# 03_-_Lattice_FPGA.net
KiCad netlist of a schematic drawn in Altium Designer
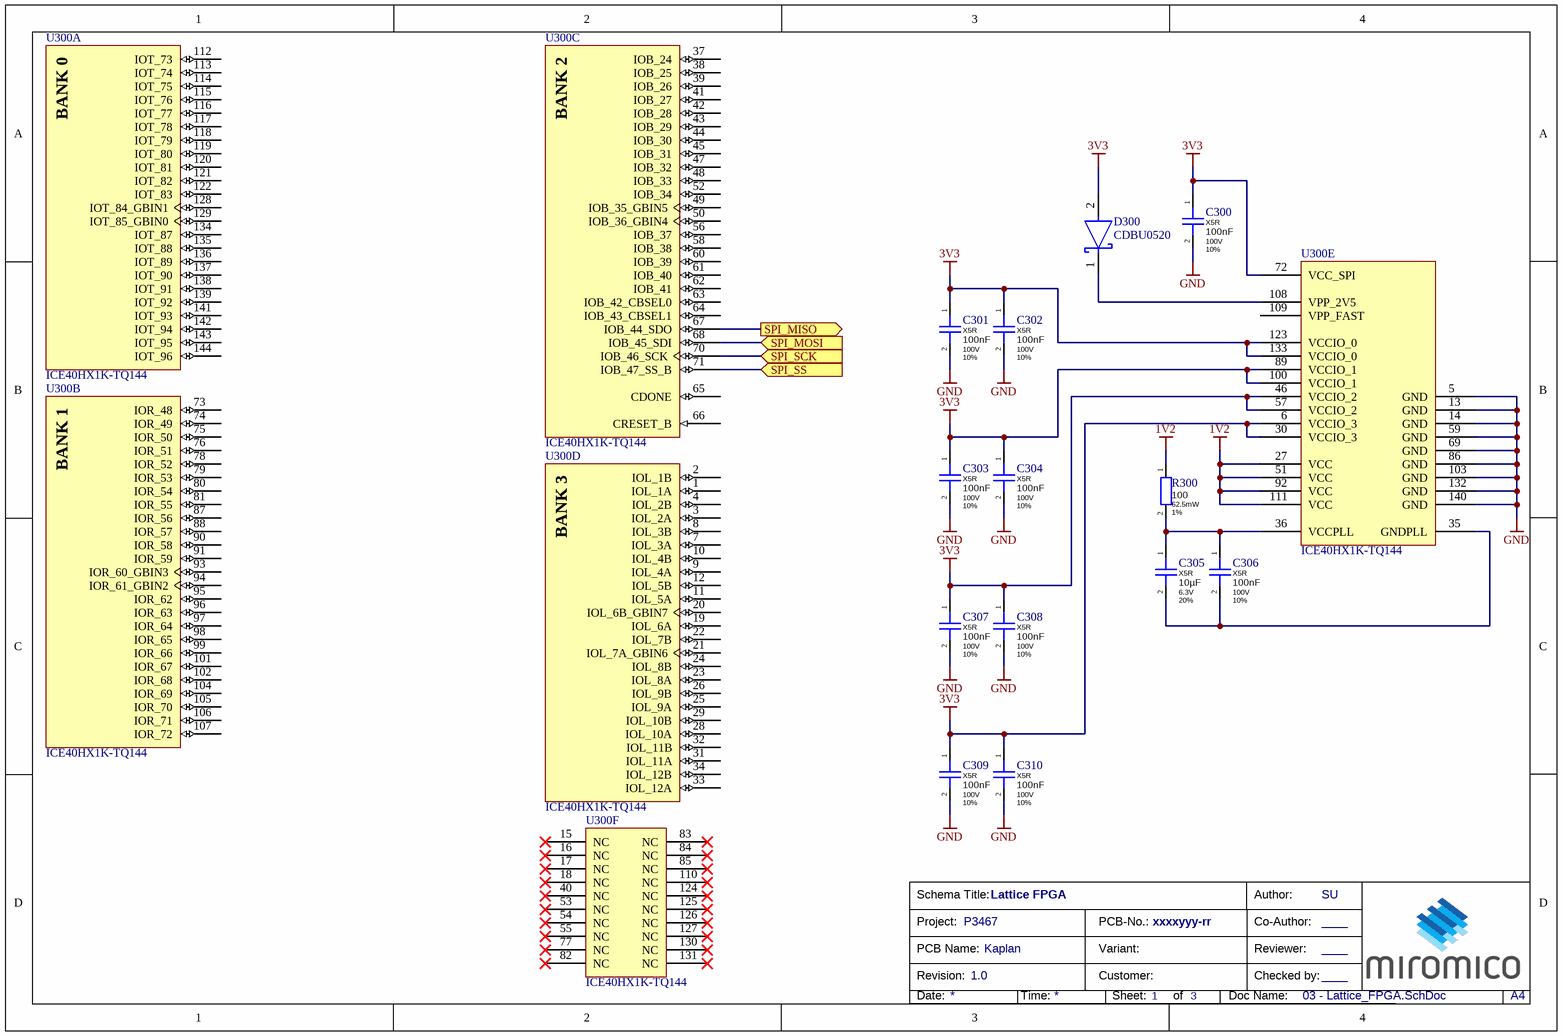
[diagram p0: 03 - Lattice_FPGA.SchDoc]

(export (version "E")
  (design (tool "Eeschema 10.0.6"))
  (components
    (comp (ref "C300")
      (value "GRM155R62A104KE14D")
      (footprint "CAPC0402(1005)60_L")
      (description "0.1µF ±10% 100V Ceramic Capacitor X5R 0402 (1005 Metric)")
      (fields
        (field (name "DIELECTRIC") "X5R")
        (field (name "CAPACITANCE") "100nF")
        (field (name "VOLTAGE RATING") "100V")
        (field (name "TOLERANCE") "10%")
        (field (name "MANUFACTURER") "Murata Electronics")
      )
      (libsource (lib "Miromico AG") (part "=Capacitance"))
    )
    (comp (ref "C301")
      (value "GRM155R62A104KE14D")
      (footprint "CAPC0402(1005)60_L")
      (description "0.1µF ±10% 100V Ceramic Capacitor X5R 0402 (1005 Metric)")
      (fields
        (field (name "DIELECTRIC") "X5R")
        (field (name "CAPACITANCE") "100nF")
        (field (name "VOLTAGE RATING") "100V")
        (field (name "TOLERANCE") "10%")
        (field (name "MANUFACTURER") "Murata Electronics")
      )
      (libsource (lib "Miromico AG") (part "=Capacitance"))
    )
    (comp (ref "C302")
      (value "GRM155R62A104KE14D")
      (footprint "CAPC0402(1005)60_L")
      (description "0.1µF ±10% 100V Ceramic Capacitor X5R 0402 (1005 Metric)")
      (fields
        (field (name "DIELECTRIC") "X5R")
        (field (name "CAPACITANCE") "100nF")
        (field (name "VOLTAGE RATING") "100V")
        (field (name "TOLERANCE") "10%")
        (field (name "MANUFACTURER") "Murata Electronics")
      )
      (libsource (lib "Miromico AG") (part "=Capacitance"))
    )
    (comp (ref "C303")
      (value "GRM155R62A104KE14D")
      (footprint "CAPC0402(1005)60_L")
      (description "0.1µF ±10% 100V Ceramic Capacitor X5R 0402 (1005 Metric)")
      (fields
        (field (name "DIELECTRIC") "X5R")
        (field (name "CAPACITANCE") "100nF")
        (field (name "VOLTAGE RATING") "100V")
        (field (name "TOLERANCE") "10%")
        (field (name "MANUFACTURER") "Murata Electronics")
      )
      (libsource (lib "Miromico AG") (part "=Capacitance"))
    )
    (comp (ref "C304")
      (value "GRM155R62A104KE14D")
      (footprint "CAPC0402(1005)60_L")
      (description "0.1µF ±10% 100V Ceramic Capacitor X5R 0402 (1005 Metric)")
      (fields
        (field (name "DIELECTRIC") "X5R")
        (field (name "CAPACITANCE") "100nF")
        (field (name "VOLTAGE RATING") "100V")
        (field (name "TOLERANCE") "10%")
        (field (name "MANUFACTURER") "Murata Electronics")
      )
      (libsource (lib "Miromico AG") (part "=Capacitance"))
    )
    (comp (ref "C305")
      (value "GRJ155R60J106ME11D")
      (footprint "CAPC0402(1005)60_L")
      (description "10µF ±20% 6.3V Ceramic Capacitor X5R 0402 (1005 Metric)")
      (fields
        (field (name "DIELECTRIC") "X5R")
        (field (name "CAPACITANCE") "10µF")
        (field (name "VOLTAGE RATING") "6.3V")
        (field (name "TOLERANCE") "20%")
        (field (name "MANUFACTURER") "Murata Electronics")
      )
      (libsource (lib "Miromico AG") (part "=Capacitance"))
    )
    (comp (ref "C306")
      (value "GRM155R62A104KE14D")
      (footprint "CAPC0402(1005)60_L")
      (description "0.1µF ±10% 100V Ceramic Capacitor X5R 0402 (1005 Metric)")
      (fields
        (field (name "DIELECTRIC") "X5R")
        (field (name "CAPACITANCE") "100nF")
        (field (name "VOLTAGE RATING") "100V")
        (field (name "TOLERANCE") "10%")
        (field (name "MANUFACTURER") "Murata Electronics")
      )
      (libsource (lib "Miromico AG") (part "=Capacitance"))
    )
    (comp (ref "C307")
      (value "GRM155R62A104KE14D")
      (footprint "CAPC0402(1005)60_L")
      (description "0.1µF ±10% 100V Ceramic Capacitor X5R 0402 (1005 Metric)")
      (fields
        (field (name "DIELECTRIC") "X5R")
        (field (name "CAPACITANCE") "100nF")
        (field (name "VOLTAGE RATING") "100V")
        (field (name "TOLERANCE") "10%")
        (field (name "MANUFACTURER") "Murata Electronics")
      )
      (libsource (lib "Miromico AG") (part "=Capacitance"))
    )
    (comp (ref "C308")
      (value "GRM155R62A104KE14D")
      (footprint "CAPC0402(1005)60_L")
      (description "0.1µF ±10% 100V Ceramic Capacitor X5R 0402 (1005 Metric)")
      (fields
        (field (name "DIELECTRIC") "X5R")
        (field (name "CAPACITANCE") "100nF")
        (field (name "VOLTAGE RATING") "100V")
        (field (name "TOLERANCE") "10%")
        (field (name "MANUFACTURER") "Murata Electronics")
      )
      (libsource (lib "Miromico AG") (part "=Capacitance"))
    )
    (comp (ref "C309")
      (value "GRM155R62A104KE14D")
      (footprint "CAPC0402(1005)60_L")
      (description "0.1µF ±10% 100V Ceramic Capacitor X5R 0402 (1005 Metric)")
      (fields
        (field (name "DIELECTRIC") "X5R")
        (field (name "CAPACITANCE") "100nF")
        (field (name "VOLTAGE RATING") "100V")
        (field (name "TOLERANCE") "10%")
        (field (name "MANUFACTURER") "Murata Electronics")
      )
      (libsource (lib "Miromico AG") (part "=Capacitance"))
    )
    (comp (ref "C310")
      (value "GRM155R62A104KE14D")
      (footprint "CAPC0402(1005)60_L")
      (description "0.1µF ±10% 100V Ceramic Capacitor X5R 0402 (1005 Metric)")
      (fields
        (field (name "DIELECTRIC") "X5R")
        (field (name "CAPACITANCE") "100nF")
        (field (name "VOLTAGE RATING") "100V")
        (field (name "TOLERANCE") "10%")
        (field (name "MANUFACTURER") "Murata Electronics")
      )
      (libsource (lib "Miromico AG") (part "=Capacitance"))
    )
    (comp (ref "D300")
      (value "CDBU0520")
      (footprint "FP-0603-SOD-523F-MFG")
      (description "DIODE SCHOTTKY 20V 500MA 0603")
      (libsource (lib "Altium Content Vault") (part "1d6ec82d83fb6aee721767c19dac4b9"))
    )
    (comp (ref "R300")
      (value "RC0402FR-07100RL")
      (footprint "RESC0402(1005)_L")
      (description "100 Ohms ±1% 0.063W, 1/16W Chip Resistor 0402 (1005 Metric)  Thick Film")
      (fields
        (field (name "RESISTANCE") "100")
        (field (name "POWER RATING") "62.5mW")
        (field (name "TOLERANCE") "1%")
        (field (name "MANUFACTURER") "Yageo")
      )
      (libsource (lib "Miromico AG") (part "=Resistance"))
    )
    (comp (ref "U300")
      (value "ICE40HX1K-TQ144")
      (footprint "LATC-TQFP-144_L")
      (fields (field (name "MANUFACTURER") "Lattice Semiconductor"))
      (libsource (lib "Altium Content Vault") (part "LATC-HX1K-TQFP-144"))
    )
  )
  (nets
    (net (code "1") (name "/SPI_MISO") (class "Default")
      (node (ref "U300") (pin "67") (pinfunction "IOB_44_SDO_67") (pintype "bidirectional"))
    )
    (net (code "2") (name "/SPI_MOSI") (class "Default")
      (node (ref "U300") (pin "68") (pinfunction "IOB_45_SDI_68") (pintype "bidirectional"))
    )
    (net (code "3") (name "/SPI_SCK") (class "Default")
      (node (ref "U300") (pin "70") (pinfunction "IOB_46_SCK_70") (pintype "bidirectional"))
    )
    (net (code "4") (name "/SPI_SS") (class "Default")
      (node (ref "U300") (pin "71") (pinfunction "IOB_47_SS_B_71") (pintype "bidirectional"))
    )
    (net (code "5") (name "1V2") (class "Default")
      (node (ref "R300") (pin "1") (pinfunction "1_1") (pintype "passive"))
      (node (ref "U300") (pin "111") (pinfunction "VCC_111") (pintype "power_in"))
      (node (ref "U300") (pin "27") (pinfunction "VCC_27") (pintype "power_in"))
      (node (ref "U300") (pin "51") (pinfunction "VCC_51") (pintype "power_in"))
      (node (ref "U300") (pin "92") (pinfunction "VCC_92") (pintype "power_in"))
    )
    (net (code "6") (name "3V3") (class "Default")
      (node (ref "C300") (pin "1") (pinfunction "1_1") (pintype "passive"))
      (node (ref "C301") (pin "1") (pinfunction "1_1") (pintype "passive"))
      (node (ref "C302") (pin "1") (pinfunction "1_1") (pintype "passive"))
      (node (ref "C303") (pin "1") (pinfunction "1_1") (pintype "passive"))
      (node (ref "C304") (pin "1") (pinfunction "1_1") (pintype "passive"))
      (node (ref "C307") (pin "1") (pinfunction "1_1") (pintype "passive"))
      (node (ref "C308") (pin "1") (pinfunction "1_1") (pintype "passive"))
      (node (ref "C309") (pin "1") (pinfunction "1_1") (pintype "passive"))
      (node (ref "C310") (pin "1") (pinfunction "1_1") (pintype "passive"))
      (node (ref "D300") (pin "2") (pinfunction "A_2") (pintype "passive"))
      (node (ref "U300") (pin "100") (pinfunction "VCCIO_1_100") (pintype "power_in"))
      (node (ref "U300") (pin "123") (pinfunction "VCCIO_0_123") (pintype "power_in"))
      (node (ref "U300") (pin "133") (pinfunction "VCCIO_0_133") (pintype "power_in"))
      (node (ref "U300") (pin "30") (pinfunction "VCCIO_3_30") (pintype "power_in"))
      (node (ref "U300") (pin "46") (pinfunction "VCCIO_2_46") (pintype "power_in"))
      (node (ref "U300") (pin "57") (pinfunction "VCCIO_2_57") (pintype "power_in"))
      (node (ref "U300") (pin "6") (pinfunction "VCCIO_3_6") (pintype "power_in"))
      (node (ref "U300") (pin "72") (pinfunction "VCC_SPI_72") (pintype "power_in"))
      (node (ref "U300") (pin "89") (pinfunction "VCCIO_1_89") (pintype "power_in"))
    )
    (net (code "7") (name "GND") (class "Default")
      (node (ref "C300") (pin "2") (pinfunction "2_2") (pintype "passive"))
      (node (ref "C301") (pin "2") (pinfunction "2_2") (pintype "passive"))
      (node (ref "C302") (pin "2") (pinfunction "2_2") (pintype "passive"))
      (node (ref "C303") (pin "2") (pinfunction "2_2") (pintype "passive"))
      (node (ref "C304") (pin "2") (pinfunction "2_2") (pintype "passive"))
      (node (ref "C307") (pin "2") (pinfunction "2_2") (pintype "passive"))
      (node (ref "C308") (pin "2") (pinfunction "2_2") (pintype "passive"))
      (node (ref "C309") (pin "2") (pinfunction "2_2") (pintype "passive"))
      (node (ref "C310") (pin "2") (pinfunction "2_2") (pintype "passive"))
      (node (ref "U300") (pin "103") (pinfunction "GND_103") (pintype "power_in"))
      (node (ref "U300") (pin "13") (pinfunction "GND_13") (pintype "power_in"))
      (node (ref "U300") (pin "132") (pinfunction "GND_132") (pintype "power_in"))
      (node (ref "U300") (pin "14") (pinfunction "GND_14") (pintype "power_in"))
      (node (ref "U300") (pin "140") (pinfunction "GND_140") (pintype "power_in"))
      (node (ref "U300") (pin "5") (pinfunction "GND_5") (pintype "power_in"))
      (node (ref "U300") (pin "59") (pinfunction "GND_59") (pintype "power_in"))
      (node (ref "U300") (pin "69") (pinfunction "GND_69") (pintype "power_in"))
      (node (ref "U300") (pin "86") (pinfunction "GND_86") (pintype "power_in"))
    )
    (net (code "8") (name "Net-(D300-C)") (class "Default")
      (node (ref "D300") (pin "1") (pinfunction "C_1") (pintype "passive"))
      (node (ref "U300") (pin "108") (pinfunction "VPP_2V5_108") (pintype "power_in"))
    )
    (net (code "9") (name "Net-(U300E-GNDPLL)") (class "Default")
      (node (ref "C305") (pin "2") (pinfunction "2_2") (pintype "passive"))
      (node (ref "C306") (pin "2") (pinfunction "2_2") (pintype "passive"))
      (node (ref "U300") (pin "35") (pinfunction "GNDPLL_35") (pintype "power_in"))
    )
    (net (code "10") (name "Net-(U300E-VCCPLL)") (class "Default")
      (node (ref "C305") (pin "1") (pinfunction "1_1") (pintype "passive"))
      (node (ref "C306") (pin "1") (pinfunction "1_1") (pintype "passive"))
      (node (ref "R300") (pin "2") (pinfunction "2_2") (pintype "passive"))
      (node (ref "U300") (pin "36") (pinfunction "VCCPLL_36") (pintype "power_in"))
    )
    (net (code "11") (name "unconnected-(U300A-IOT_73-Pad112)") (class "Default")
      (node (ref "U300") (pin "112") (pinfunction "IOT_73_112") (pintype "bidirectional"))
    )
    (net (code "12") (name "unconnected-(U300A-IOT_74-Pad113)") (class "Default")
      (node (ref "U300") (pin "113") (pinfunction "IOT_74_113") (pintype "bidirectional"))
    )
    (net (code "13") (name "unconnected-(U300A-IOT_75-Pad114)") (class "Default")
      (node (ref "U300") (pin "114") (pinfunction "IOT_75_114") (pintype "bidirectional"))
    )
    (net (code "14") (name "unconnected-(U300A-IOT_76-Pad115)") (class "Default")
      (node (ref "U300") (pin "115") (pinfunction "IOT_76_115") (pintype "bidirectional"))
    )
    (net (code "15") (name "unconnected-(U300A-IOT_77-Pad116)") (class "Default")
      (node (ref "U300") (pin "116") (pinfunction "IOT_77_116") (pintype "bidirectional"))
    )
    (net (code "16") (name "unconnected-(U300A-IOT_78-Pad117)") (class "Default")
      (node (ref "U300") (pin "117") (pinfunction "IOT_78_117") (pintype "bidirectional"))
    )
    (net (code "17") (name "unconnected-(U300A-IOT_79-Pad118)") (class "Default")
      (node (ref "U300") (pin "118") (pinfunction "IOT_79_118") (pintype "bidirectional"))
    )
    (net (code "18") (name "unconnected-(U300A-IOT_80-Pad119)") (class "Default")
      (node (ref "U300") (pin "119") (pinfunction "IOT_80_119") (pintype "bidirectional"))
    )
    (net (code "19") (name "unconnected-(U300A-IOT_81-Pad120)") (class "Default")
      (node (ref "U300") (pin "120") (pinfunction "IOT_81_120") (pintype "bidirectional"))
    )
    (net (code "20") (name "unconnected-(U300A-IOT_82-Pad121)") (class "Default")
      (node (ref "U300") (pin "121") (pinfunction "IOT_82_121") (pintype "bidirectional"))
    )
    (net (code "21") (name "unconnected-(U300A-IOT_83-Pad122)") (class "Default")
      (node (ref "U300") (pin "122") (pinfunction "IOT_83_122") (pintype "bidirectional"))
    )
    (net (code "22") (name "unconnected-(U300A-IOT_84_GBIN1-Pad128)") (class "Default")
      (node (ref "U300") (pin "128") (pinfunction "IOT_84_GBIN1_128") (pintype "bidirectional"))
    )
    (net (code "23") (name "unconnected-(U300A-IOT_85_GBIN0-Pad129)") (class "Default")
      (node (ref "U300") (pin "129") (pinfunction "IOT_85_GBIN0_129") (pintype "bidirectional"))
    )
    (net (code "24") (name "unconnected-(U300A-IOT_87-Pad134)") (class "Default")
      (node (ref "U300") (pin "134") (pinfunction "IOT_87_134") (pintype "bidirectional"))
    )
    (net (code "25") (name "unconnected-(U300A-IOT_88-Pad135)") (class "Default")
      (node (ref "U300") (pin "135") (pinfunction "IOT_88_135") (pintype "bidirectional"))
    )
    (net (code "26") (name "unconnected-(U300A-IOT_89-Pad136)") (class "Default")
      (node (ref "U300") (pin "136") (pinfunction "IOT_89_136") (pintype "bidirectional"))
    )
    (net (code "27") (name "unconnected-(U300A-IOT_90-Pad137)") (class "Default")
      (node (ref "U300") (pin "137") (pinfunction "IOT_90_137") (pintype "bidirectional"))
    )
    (net (code "28") (name "unconnected-(U300A-IOT_91-Pad138)") (class "Default")
      (node (ref "U300") (pin "138") (pinfunction "IOT_91_138") (pintype "bidirectional"))
    )
    (net (code "29") (name "unconnected-(U300A-IOT_92-Pad139)") (class "Default")
      (node (ref "U300") (pin "139") (pinfunction "IOT_92_139") (pintype "bidirectional"))
    )
    (net (code "30") (name "unconnected-(U300A-IOT_93-Pad141)") (class "Default")
      (node (ref "U300") (pin "141") (pinfunction "IOT_93_141") (pintype "bidirectional"))
    )
    (net (code "31") (name "unconnected-(U300A-IOT_94-Pad142)") (class "Default")
      (node (ref "U300") (pin "142") (pinfunction "IOT_94_142") (pintype "bidirectional"))
    )
    (net (code "32") (name "unconnected-(U300A-IOT_95-Pad143)") (class "Default")
      (node (ref "U300") (pin "143") (pinfunction "IOT_95_143") (pintype "bidirectional"))
    )
    (net (code "33") (name "unconnected-(U300A-IOT_96-Pad144)") (class "Default")
      (node (ref "U300") (pin "144") (pinfunction "IOT_96_144") (pintype "bidirectional"))
    )
    (net (code "34") (name "unconnected-(U300B-IOR_48-Pad73)") (class "Default")
      (node (ref "U300") (pin "73") (pinfunction "IOR_48_73") (pintype "bidirectional"))
    )
    (net (code "35") (name "unconnected-(U300B-IOR_49-Pad74)") (class "Default")
      (node (ref "U300") (pin "74") (pinfunction "IOR_49_74") (pintype "bidirectional"))
    )
    (net (code "36") (name "unconnected-(U300B-IOR_50-Pad75)") (class "Default")
      (node (ref "U300") (pin "75") (pinfunction "IOR_50_75") (pintype "bidirectional"))
    )
    (net (code "37") (name "unconnected-(U300B-IOR_51-Pad76)") (class "Default")
      (node (ref "U300") (pin "76") (pinfunction "IOR_51_76") (pintype "bidirectional"))
    )
    (net (code "38") (name "unconnected-(U300B-IOR_52-Pad78)") (class "Default")
      (node (ref "U300") (pin "78") (pinfunction "IOR_52_78") (pintype "bidirectional"))
    )
    (net (code "39") (name "unconnected-(U300B-IOR_53-Pad79)") (class "Default")
      (node (ref "U300") (pin "79") (pinfunction "IOR_53_79") (pintype "bidirectional"))
    )
    (net (code "40") (name "unconnected-(U300B-IOR_54-Pad80)") (class "Default")
      (node (ref "U300") (pin "80") (pinfunction "IOR_54_80") (pintype "bidirectional"))
    )
    (net (code "41") (name "unconnected-(U300B-IOR_55-Pad81)") (class "Default")
      (node (ref "U300") (pin "81") (pinfunction "IOR_55_81") (pintype "bidirectional"))
    )
    (net (code "42") (name "unconnected-(U300B-IOR_56-Pad87)") (class "Default")
      (node (ref "U300") (pin "87") (pinfunction "IOR_56_87") (pintype "bidirectional"))
    )
    (net (code "43") (name "unconnected-(U300B-IOR_57-Pad88)") (class "Default")
      (node (ref "U300") (pin "88") (pinfunction "IOR_57_88") (pintype "bidirectional"))
    )
    (net (code "44") (name "unconnected-(U300B-IOR_58-Pad90)") (class "Default")
      (node (ref "U300") (pin "90") (pinfunction "IOR_58_90") (pintype "bidirectional"))
    )
    (net (code "45") (name "unconnected-(U300B-IOR_59-Pad91)") (class "Default")
      (node (ref "U300") (pin "91") (pinfunction "IOR_59_91") (pintype "bidirectional"))
    )
    (net (code "46") (name "unconnected-(U300B-IOR_60_GBIN3-Pad93)") (class "Default")
      (node (ref "U300") (pin "93") (pinfunction "IOR_60_GBIN3_93") (pintype "bidirectional"))
    )
    (net (code "47") (name "unconnected-(U300B-IOR_61_GBIN2-Pad94)") (class "Default")
      (node (ref "U300") (pin "94") (pinfunction "IOR_61_GBIN2_94") (pintype "bidirectional"))
    )
    (net (code "48") (name "unconnected-(U300B-IOR_62-Pad95)") (class "Default")
      (node (ref "U300") (pin "95") (pinfunction "IOR_62_95") (pintype "bidirectional"))
    )
    (net (code "49") (name "unconnected-(U300B-IOR_63-Pad96)") (class "Default")
      (node (ref "U300") (pin "96") (pinfunction "IOR_63_96") (pintype "bidirectional"))
    )
    (net (code "50") (name "unconnected-(U300B-IOR_64-Pad97)") (class "Default")
      (node (ref "U300") (pin "97") (pinfunction "IOR_64_97") (pintype "bidirectional"))
    )
    (net (code "51") (name "unconnected-(U300B-IOR_65-Pad98)") (class "Default")
      (node (ref "U300") (pin "98") (pinfunction "IOR_65_98") (pintype "bidirectional"))
    )
    (net (code "52") (name "unconnected-(U300B-IOR_66-Pad99)") (class "Default")
      (node (ref "U300") (pin "99") (pinfunction "IOR_66_99") (pintype "bidirectional"))
    )
    (net (code "53") (name "unconnected-(U300B-IOR_67-Pad101)") (class "Default")
      (node (ref "U300") (pin "101") (pinfunction "IOR_67_101") (pintype "bidirectional"))
    )
    (net (code "54") (name "unconnected-(U300B-IOR_68-Pad102)") (class "Default")
      (node (ref "U300") (pin "102") (pinfunction "IOR_68_102") (pintype "bidirectional"))
    )
    (net (code "55") (name "unconnected-(U300B-IOR_69-Pad104)") (class "Default")
      (node (ref "U300") (pin "104") (pinfunction "IOR_69_104") (pintype "bidirectional"))
    )
    (net (code "56") (name "unconnected-(U300B-IOR_70-Pad105)") (class "Default")
      (node (ref "U300") (pin "105") (pinfunction "IOR_70_105") (pintype "bidirectional"))
    )
    (net (code "57") (name "unconnected-(U300B-IOR_71-Pad106)") (class "Default")
      (node (ref "U300") (pin "106") (pinfunction "IOR_71_106") (pintype "bidirectional"))
    )
    (net (code "58") (name "unconnected-(U300B-IOR_72-Pad107)") (class "Default")
      (node (ref "U300") (pin "107") (pinfunction "IOR_72_107") (pintype "bidirectional"))
    )
    (net (code "59") (name "unconnected-(U300C-CDONE-Pad65)") (class "Default")
      (node (ref "U300") (pin "65") (pinfunction "CDONE_65") (pintype "bidirectional"))
    )
    (net (code "60") (name "unconnected-(U300C-CRESET_B-Pad66)") (class "Default")
      (node (ref "U300") (pin "66") (pinfunction "CRESET_B_66") (pintype "input"))
    )
    (net (code "61") (name "unconnected-(U300C-IOB_24-Pad37)") (class "Default")
      (node (ref "U300") (pin "37") (pinfunction "IOB_24_37") (pintype "bidirectional"))
    )
    (net (code "62") (name "unconnected-(U300C-IOB_25-Pad38)") (class "Default")
      (node (ref "U300") (pin "38") (pinfunction "IOB_25_38") (pintype "bidirectional"))
    )
    (net (code "63") (name "unconnected-(U300C-IOB_26-Pad39)") (class "Default")
      (node (ref "U300") (pin "39") (pinfunction "IOB_26_39") (pintype "bidirectional"))
    )
    (net (code "64") (name "unconnected-(U300C-IOB_27-Pad41)") (class "Default")
      (node (ref "U300") (pin "41") (pinfunction "IOB_27_41") (pintype "bidirectional"))
    )
    (net (code "65") (name "unconnected-(U300C-IOB_28-Pad42)") (class "Default")
      (node (ref "U300") (pin "42") (pinfunction "IOB_28_42") (pintype "bidirectional"))
    )
    (net (code "66") (name "unconnected-(U300C-IOB_29-Pad43)") (class "Default")
      (node (ref "U300") (pin "43") (pinfunction "IOB_29_43") (pintype "bidirectional"))
    )
    (net (code "67") (name "unconnected-(U300C-IOB_30-Pad44)") (class "Default")
      (node (ref "U300") (pin "44") (pinfunction "IOB_30_44") (pintype "bidirectional"))
    )
    (net (code "68") (name "unconnected-(U300C-IOB_31-Pad45)") (class "Default")
      (node (ref "U300") (pin "45") (pinfunction "IOB_31_45") (pintype "bidirectional"))
    )
    (net (code "69") (name "unconnected-(U300C-IOB_32-Pad47)") (class "Default")
      (node (ref "U300") (pin "47") (pinfunction "IOB_32_47") (pintype "bidirectional"))
    )
    (net (code "70") (name "unconnected-(U300C-IOB_33-Pad48)") (class "Default")
      (node (ref "U300") (pin "48") (pinfunction "IOB_33_48") (pintype "bidirectional"))
    )
    (net (code "71") (name "unconnected-(U300C-IOB_34-Pad52)") (class "Default")
      (node (ref "U300") (pin "52") (pinfunction "IOB_34_52") (pintype "bidirectional"))
    )
    (net (code "72") (name "unconnected-(U300C-IOB_35_GBIN5-Pad49)") (class "Default")
      (node (ref "U300") (pin "49") (pinfunction "IOB_35_GBIN5_49") (pintype "bidirectional"))
    )
    (net (code "73") (name "unconnected-(U300C-IOB_36_GBIN4-Pad50)") (class "Default")
      (node (ref "U300") (pin "50") (pinfunction "IOB_36_GBIN4_50") (pintype "bidirectional"))
    )
    (net (code "74") (name "unconnected-(U300C-IOB_37-Pad56)") (class "Default")
      (node (ref "U300") (pin "56") (pinfunction "IOB_37_56") (pintype "bidirectional"))
    )
    (net (code "75") (name "unconnected-(U300C-IOB_38-Pad58)") (class "Default")
      (node (ref "U300") (pin "58") (pinfunction "IOB_38_58") (pintype "bidirectional"))
    )
    (net (code "76") (name "unconnected-(U300C-IOB_39-Pad60)") (class "Default")
      (node (ref "U300") (pin "60") (pinfunction "IOB_39_60") (pintype "bidirectional"))
    )
    (net (code "77") (name "unconnected-(U300C-IOB_40-Pad61)") (class "Default")
      (node (ref "U300") (pin "61") (pinfunction "IOB_40_61") (pintype "bidirectional"))
    )
    (net (code "78") (name "unconnected-(U300C-IOB_41-Pad62)") (class "Default")
      (node (ref "U300") (pin "62") (pinfunction "IOB_41_62") (pintype "bidirectional"))
    )
    (net (code "79") (name "unconnected-(U300C-IOB_42_CBSEL0-Pad63)") (class "Default")
      (node (ref "U300") (pin "63") (pinfunction "IOB_42_CBSEL0_63") (pintype "bidirectional"))
    )
    (net (code "80") (name "unconnected-(U300C-IOB_43_CBSEL1-Pad64)") (class "Default")
      (node (ref "U300") (pin "64") (pinfunction "IOB_43_CBSEL1_64") (pintype "bidirectional"))
    )
    (net (code "81") (name "unconnected-(U300D-IOL_1A-Pad1)") (class "Default")
      (node (ref "U300") (pin "1") (pinfunction "IOL_1A_1") (pintype "bidirectional"))
    )
    (net (code "82") (name "unconnected-(U300D-IOL_1B-Pad2)") (class "Default")
      (node (ref "U300") (pin "2") (pinfunction "IOL_1B_2") (pintype "bidirectional"))
    )
    (net (code "83") (name "unconnected-(U300D-IOL_2A-Pad3)") (class "Default")
      (node (ref "U300") (pin "3") (pinfunction "IOL_2A_3") (pintype "bidirectional"))
    )
    (net (code "84") (name "unconnected-(U300D-IOL_2B-Pad4)") (class "Default")
      (node (ref "U300") (pin "4") (pinfunction "IOL_2B_4") (pintype "bidirectional"))
    )
    (net (code "85") (name "unconnected-(U300D-IOL_3A-Pad7)") (class "Default")
      (node (ref "U300") (pin "7") (pinfunction "IOL_3A_7") (pintype "bidirectional"))
    )
    (net (code "86") (name "unconnected-(U300D-IOL_3B-Pad8)") (class "Default")
      (node (ref "U300") (pin "8") (pinfunction "IOL_3B_8") (pintype "bidirectional"))
    )
    (net (code "87") (name "unconnected-(U300D-IOL_4A-Pad9)") (class "Default")
      (node (ref "U300") (pin "9") (pinfunction "IOL_4A_9") (pintype "bidirectional"))
    )
    (net (code "88") (name "unconnected-(U300D-IOL_4B-Pad10)") (class "Default")
      (node (ref "U300") (pin "10") (pinfunction "IOL_4B_10") (pintype "bidirectional"))
    )
    (net (code "89") (name "unconnected-(U300D-IOL_5A-Pad11)") (class "Default")
      (node (ref "U300") (pin "11") (pinfunction "IOL_5A_11") (pintype "bidirectional"))
    )
    (net (code "90") (name "unconnected-(U300D-IOL_5B-Pad12)") (class "Default")
      (node (ref "U300") (pin "12") (pinfunction "IOL_5B_12") (pintype "bidirectional"))
    )
    (net (code "91") (name "unconnected-(U300D-IOL_6A-Pad19)") (class "Default")
      (node (ref "U300") (pin "19") (pinfunction "IOL_6A_19") (pintype "bidirectional"))
    )
    (net (code "92") (name "unconnected-(U300D-IOL_6B_GBIN7-Pad20)") (class "Default")
      (node (ref "U300") (pin "20") (pinfunction "IOL_6B_GBIN7_20") (pintype "bidirectional"))
    )
    (net (code "93") (name "unconnected-(U300D-IOL_7A_GBIN6-Pad21)") (class "Default")
      (node (ref "U300") (pin "21") (pinfunction "IOL_7A_GBIN6_21") (pintype "bidirectional"))
    )
    (net (code "94") (name "unconnected-(U300D-IOL_7B-Pad22)") (class "Default")
      (node (ref "U300") (pin "22") (pinfunction "IOL_7B_22") (pintype "bidirectional"))
    )
    (net (code "95") (name "unconnected-(U300D-IOL_8A-Pad23)") (class "Default")
      (node (ref "U300") (pin "23") (pinfunction "IOL_8A_23") (pintype "bidirectional"))
    )
    (net (code "96") (name "unconnected-(U300D-IOL_8B-Pad24)") (class "Default")
      (node (ref "U300") (pin "24") (pinfunction "IOL_8B_24") (pintype "bidirectional"))
    )
    (net (code "97") (name "unconnected-(U300D-IOL_9A-Pad25)") (class "Default")
      (node (ref "U300") (pin "25") (pinfunction "IOL_9A_25") (pintype "bidirectional"))
    )
    (net (code "98") (name "unconnected-(U300D-IOL_9B-Pad26)") (class "Default")
      (node (ref "U300") (pin "26") (pinfunction "IOL_9B_26") (pintype "bidirectional"))
    )
    (net (code "99") (name "unconnected-(U300D-IOL_10A-Pad28)") (class "Default")
      (node (ref "U300") (pin "28") (pinfunction "IOL_10A_28") (pintype "bidirectional"))
    )
    (net (code "100") (name "unconnected-(U300D-IOL_10B-Pad29)") (class "Default")
      (node (ref "U300") (pin "29") (pinfunction "IOL_10B_29") (pintype "bidirectional"))
    )
    (net (code "101") (name "unconnected-(U300D-IOL_11A-Pad31)") (class "Default")
      (node (ref "U300") (pin "31") (pinfunction "IOL_11A_31") (pintype "bidirectional"))
    )
    (net (code "102") (name "unconnected-(U300D-IOL_11B-Pad32)") (class "Default")
      (node (ref "U300") (pin "32") (pinfunction "IOL_11B_32") (pintype "bidirectional"))
    )
    (net (code "103") (name "unconnected-(U300D-IOL_12A-Pad33)") (class "Default")
      (node (ref "U300") (pin "33") (pinfunction "IOL_12A_33") (pintype "bidirectional"))
    )
    (net (code "104") (name "unconnected-(U300D-IOL_12B-Pad34)") (class "Default")
      (node (ref "U300") (pin "34") (pinfunction "IOL_12B_34") (pintype "bidirectional"))
    )
    (net (code "105") (name "unconnected-(U300E-VPP_FAST-Pad109)") (class "Default")
      (node (ref "U300") (pin "109") (pinfunction "VPP_FAST_109") (pintype "power_in"))
    )
    (net (code "106") (name "unconnected-(U300F-NC-Pad15)") (class "Default")
      (node (ref "U300") (pin "15") (pinfunction "NC_15") (pintype "passive+no_connect"))
    )
    (net (code "107") (name "unconnected-(U300F-NC-Pad16)") (class "Default")
      (node (ref "U300") (pin "16") (pinfunction "NC_16") (pintype "passive+no_connect"))
    )
    (net (code "108") (name "unconnected-(U300F-NC-Pad17)") (class "Default")
      (node (ref "U300") (pin "17") (pinfunction "NC_17") (pintype "passive+no_connect"))
    )
    (net (code "109") (name "unconnected-(U300F-NC-Pad18)") (class "Default")
      (node (ref "U300") (pin "18") (pinfunction "NC_18") (pintype "passive+no_connect"))
    )
    (net (code "110") (name "unconnected-(U300F-NC-Pad40)") (class "Default")
      (node (ref "U300") (pin "40") (pinfunction "NC_40") (pintype "passive+no_connect"))
    )
    (net (code "111") (name "unconnected-(U300F-NC-Pad53)") (class "Default")
      (node (ref "U300") (pin "53") (pinfunction "NC_53") (pintype "passive+no_connect"))
    )
    (net (code "112") (name "unconnected-(U300F-NC-Pad54)") (class "Default")
      (node (ref "U300") (pin "54") (pinfunction "NC_54") (pintype "passive+no_connect"))
    )
    (net (code "113") (name "unconnected-(U300F-NC-Pad55)") (class "Default")
      (node (ref "U300") (pin "55") (pinfunction "NC_55") (pintype "passive+no_connect"))
    )
    (net (code "114") (name "unconnected-(U300F-NC-Pad77)") (class "Default")
      (node (ref "U300") (pin "77") (pinfunction "NC_77") (pintype "passive+no_connect"))
    )
    (net (code "115") (name "unconnected-(U300F-NC-Pad82)") (class "Default")
      (node (ref "U300") (pin "82") (pinfunction "NC_82") (pintype "passive+no_connect"))
    )
    (net (code "116") (name "unconnected-(U300F-NC-Pad83)") (class "Default")
      (node (ref "U300") (pin "83") (pinfunction "NC_83") (pintype "passive+no_connect"))
    )
    (net (code "117") (name "unconnected-(U300F-NC-Pad84)") (class "Default")
      (node (ref "U300") (pin "84") (pinfunction "NC_84") (pintype "passive+no_connect"))
    )
    (net (code "118") (name "unconnected-(U300F-NC-Pad85)") (class "Default")
      (node (ref "U300") (pin "85") (pinfunction "NC_85") (pintype "passive+no_connect"))
    )
    (net (code "119") (name "unconnected-(U300F-NC-Pad110)") (class "Default")
      (node (ref "U300") (pin "110") (pinfunction "NC_110") (pintype "passive+no_connect"))
    )
    (net (code "120") (name "unconnected-(U300F-NC-Pad124)") (class "Default")
      (node (ref "U300") (pin "124") (pinfunction "NC_124") (pintype "passive+no_connect"))
    )
    (net (code "121") (name "unconnected-(U300F-NC-Pad125)") (class "Default")
      (node (ref "U300") (pin "125") (pinfunction "NC_125") (pintype "passive+no_connect"))
    )
    (net (code "122") (name "unconnected-(U300F-NC-Pad126)") (class "Default")
      (node (ref "U300") (pin "126") (pinfunction "NC_126") (pintype "passive+no_connect"))
    )
    (net (code "123") (name "unconnected-(U300F-NC-Pad127)") (class "Default")
      (node (ref "U300") (pin "127") (pinfunction "NC_127") (pintype "passive+no_connect"))
    )
    (net (code "124") (name "unconnected-(U300F-NC-Pad130)") (class "Default")
      (node (ref "U300") (pin "130") (pinfunction "NC_130") (pintype "passive+no_connect"))
    )
    (net (code "125") (name "unconnected-(U300F-NC-Pad131)") (class "Default")
      (node (ref "U300") (pin "131") (pinfunction "NC_131") (pintype "passive+no_connect"))
    )
  )
)
